# Electric_schematic.net
KiCad netlist of a schematic drawn in Altium Designer
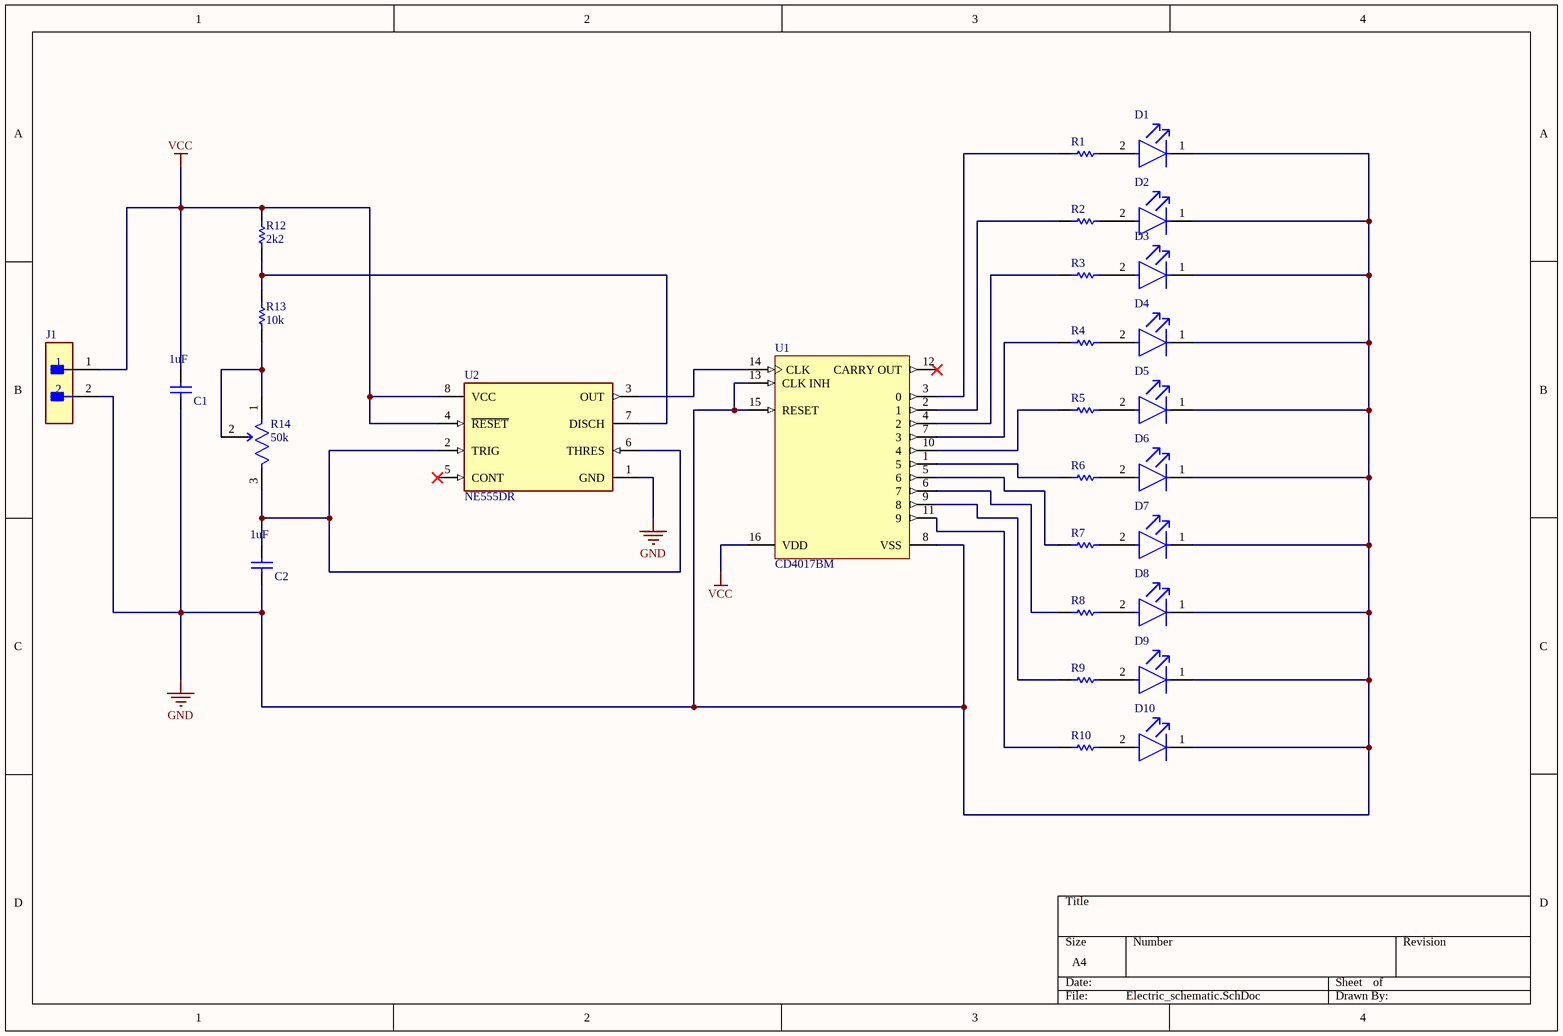
[diagram p0: Electric_schematic.SchDoc]

(export (version "E")
  (design (tool "Eeschema 10.0.6"))
  (components
    (comp (ref "C1")
      (value "1uF")
      (footprint "CAPC2013X135X45LL10T25")
      (fields (field (name "MANUFACTURER") "Murata") (field (name "PART NUMBER") "GRM21BR71H105KA12L"))
      (libsource (lib "Altium Content Vault") (part "CAP"))
    )
    (comp (ref "C2")
      (value "1uF")
      (footprint "CAPC2013X135X45LL10T25")
      (fields (field (name "MANUFACTURER") "Murata") (field (name "PART NUMBER") "GRM21BR71H105KA12L"))
      (libsource (lib "Altium Content Vault") (part "CAP"))
    )
    (comp (ref "D1")
      (value "HLMP-1301")
      (footprint "FP-HLMP-1301-MFG")
      (description "LED RED DIFFUSED T-1 T/H")
      (fields
        (field (name "OCTOPART") "https://octopart.com/hlmp-1301-broadcom-71130345")
        (field (name "MANUFACTURER") "Broadcom")
      )
      (libsource (lib "Altium Content Vault") (part "8706943c75ba83719d021d2fdc84c58"))
    )
    (comp (ref "D2")
      (value "HLMP-1301")
      (footprint "FP-HLMP-1301-MFG")
      (description "LED RED DIFFUSED T-1 T/H")
      (fields
        (field (name "OCTOPART") "https://octopart.com/hlmp-1301-broadcom-71130345")
        (field (name "MANUFACTURER") "Broadcom")
      )
      (libsource (lib "Altium Content Vault") (part "8706943c75ba83719d021d2fdc84c58"))
    )
    (comp (ref "D3")
      (value "HLMP-1301")
      (footprint "FP-HLMP-1301-MFG")
      (description "LED RED DIFFUSED T-1 T/H")
      (fields
        (field (name "OCTOPART") "https://octopart.com/hlmp-1301-broadcom-71130345")
        (field (name "MANUFACTURER") "Broadcom")
      )
      (libsource (lib "Altium Content Vault") (part "8706943c75ba83719d021d2fdc84c58"))
    )
    (comp (ref "D4")
      (value "HLMP-1301")
      (footprint "FP-HLMP-1301-MFG")
      (description "LED RED DIFFUSED T-1 T/H")
      (fields
        (field (name "OCTOPART") "https://octopart.com/hlmp-1301-broadcom-71130345")
        (field (name "MANUFACTURER") "Broadcom")
      )
      (libsource (lib "Altium Content Vault") (part "8706943c75ba83719d021d2fdc84c58"))
    )
    (comp (ref "D5")
      (value "HLMP-1301")
      (footprint "FP-HLMP-1301-MFG")
      (description "LED RED DIFFUSED T-1 T/H")
      (fields
        (field (name "OCTOPART") "https://octopart.com/hlmp-1301-broadcom-71130345")
        (field (name "MANUFACTURER") "Broadcom")
      )
      (libsource (lib "Altium Content Vault") (part "8706943c75ba83719d021d2fdc84c58"))
    )
    (comp (ref "D6")
      (value "HLMP-1301")
      (footprint "FP-HLMP-1301-MFG")
      (description "LED RED DIFFUSED T-1 T/H")
      (fields
        (field (name "OCTOPART") "https://octopart.com/hlmp-1301-broadcom-71130345")
        (field (name "MANUFACTURER") "Broadcom")
      )
      (libsource (lib "Altium Content Vault") (part "8706943c75ba83719d021d2fdc84c58"))
    )
    (comp (ref "D7")
      (value "HLMP-1301")
      (footprint "FP-HLMP-1301-MFG")
      (description "LED RED DIFFUSED T-1 T/H")
      (fields
        (field (name "OCTOPART") "https://octopart.com/hlmp-1301-broadcom-71130345")
        (field (name "MANUFACTURER") "Broadcom")
      )
      (libsource (lib "Altium Content Vault") (part "8706943c75ba83719d021d2fdc84c58"))
    )
    (comp (ref "D8")
      (value "HLMP-1301")
      (footprint "FP-HLMP-1301-MFG")
      (description "LED RED DIFFUSED T-1 T/H")
      (fields
        (field (name "OCTOPART") "https://octopart.com/hlmp-1301-broadcom-71130345")
        (field (name "MANUFACTURER") "Broadcom")
      )
      (libsource (lib "Altium Content Vault") (part "8706943c75ba83719d021d2fdc84c58"))
    )
    (comp (ref "D9")
      (value "HLMP-1301")
      (footprint "FP-HLMP-1301-MFG")
      (description "LED RED DIFFUSED T-1 T/H")
      (fields
        (field (name "OCTOPART") "https://octopart.com/hlmp-1301-broadcom-71130345")
        (field (name "MANUFACTURER") "Broadcom")
      )
      (libsource (lib "Altium Content Vault") (part "8706943c75ba83719d021d2fdc84c58"))
    )
    (comp (ref "D10")
      (value "HLMP-1301")
      (footprint "FP-HLMP-1301-MFG")
      (description "LED RED DIFFUSED T-1 T/H")
      (fields
        (field (name "OCTOPART") "https://octopart.com/hlmp-1301-broadcom-71130345")
        (field (name "MANUFACTURER") "Broadcom")
      )
      (libsource (lib "Altium Content Vault") (part "8706943c75ba83719d021d2fdc84c58"))
    )
    (comp (ref "J1")
      (value "M20-9990246")
      (footprint "FP-M20-9990246-MFG")
      (description "CONN HEADER VERT 2POS 2.54MM")
      (fields
        (field (name "OCTOPART") "https://octopart.com/m20-9990246-harwin-2590635")
        (field (name "MANUFACTURER") "Harwin")
      )
      (libsource (lib "Altium Content Vault") (part "3bc925449376181038e59eaffc5286c"))
    )
    (comp (ref "R1")
      (value "RC0805FR-071KL")
      (footprint "RESC2013X60X35ML10T20")
      (description "Chip Resistor, 1 KOhm, +/- 1%, 125 mW, -55 to 155 degC, 0805 (2012 Metric), RoHS, Tape and Reel")
      (fields (field (name "TOLERANCE") "1%") (field (name "MANUFACTURER") "Yageo"))
      (libsource (lib "Altium Content Vault") (part "RES-2"))
    )
    (comp (ref "R2")
      (value "RC0805FR-071KL")
      (footprint "RESC2013X60X35ML10T20")
      (description "Chip Resistor, 1 KOhm, +/- 1%, 125 mW, -55 to 155 degC, 0805 (2012 Metric), RoHS, Tape and Reel")
      (fields (field (name "TOLERANCE") "1%") (field (name "MANUFACTURER") "Yageo"))
      (libsource (lib "Altium Content Vault") (part "RES-2"))
    )
    (comp (ref "R3")
      (value "RC0805FR-071KL")
      (footprint "RESC2013X60X35ML10T20")
      (description "Chip Resistor, 1 KOhm, +/- 1%, 125 mW, -55 to 155 degC, 0805 (2012 Metric), RoHS, Tape and Reel")
      (fields (field (name "TOLERANCE") "1%") (field (name "MANUFACTURER") "Yageo"))
      (libsource (lib "Altium Content Vault") (part "RES-2"))
    )
    (comp (ref "R4")
      (value "RC0805FR-071KL")
      (footprint "RESC2013X60X35ML10T20")
      (description "Chip Resistor, 1 KOhm, +/- 1%, 125 mW, -55 to 155 degC, 0805 (2012 Metric), RoHS, Tape and Reel")
      (fields (field (name "TOLERANCE") "1%") (field (name "MANUFACTURER") "Yageo"))
      (libsource (lib "Altium Content Vault") (part "RES-2"))
    )
    (comp (ref "R5")
      (value "RC0805FR-071KL")
      (footprint "RESC2013X60X35ML10T20")
      (description "Chip Resistor, 1 KOhm, +/- 1%, 125 mW, -55 to 155 degC, 0805 (2012 Metric), RoHS, Tape and Reel")
      (fields (field (name "TOLERANCE") "1%") (field (name "MANUFACTURER") "Yageo"))
      (libsource (lib "Altium Content Vault") (part "RES-2"))
    )
    (comp (ref "R6")
      (value "RC0805FR-071KL")
      (footprint "RESC2013X60X35ML10T20")
      (description "Chip Resistor, 1 KOhm, +/- 1%, 125 mW, -55 to 155 degC, 0805 (2012 Metric), RoHS, Tape and Reel")
      (fields (field (name "TOLERANCE") "1%") (field (name "MANUFACTURER") "Yageo"))
      (libsource (lib "Altium Content Vault") (part "RES-2"))
    )
    (comp (ref "R7")
      (value "RC0805FR-071KL")
      (footprint "RESC2013X60X35ML10T20")
      (description "Chip Resistor, 1 KOhm, +/- 1%, 125 mW, -55 to 155 degC, 0805 (2012 Metric), RoHS, Tape and Reel")
      (fields (field (name "TOLERANCE") "1%") (field (name "MANUFACTURER") "Yageo"))
      (libsource (lib "Altium Content Vault") (part "RES-2"))
    )
    (comp (ref "R8")
      (value "RC0805FR-071KL")
      (footprint "RESC2013X60X35ML10T20")
      (description "Chip Resistor, 1 KOhm, +/- 1%, 125 mW, -55 to 155 degC, 0805 (2012 Metric), RoHS, Tape and Reel")
      (fields (field (name "TOLERANCE") "1%") (field (name "MANUFACTURER") "Yageo"))
      (libsource (lib "Altium Content Vault") (part "RES-2"))
    )
    (comp (ref "R9")
      (value "RC0805FR-071KL")
      (footprint "RESC2013X60X35ML10T20")
      (description "Chip Resistor, 1 KOhm, +/- 1%, 125 mW, -55 to 155 degC, 0805 (2012 Metric), RoHS, Tape and Reel")
      (fields (field (name "TOLERANCE") "1%") (field (name "MANUFACTURER") "Yageo"))
      (libsource (lib "Altium Content Vault") (part "RES-2"))
    )
    (comp (ref "R10")
      (value "RC0805FR-071KL")
      (footprint "RESC2013X60X35ML10T20")
      (description "Chip Resistor, 1 KOhm, +/- 1%, 125 mW, -55 to 155 degC, 0805 (2012 Metric), RoHS, Tape and Reel")
      (fields (field (name "TOLERANCE") "1%") (field (name "MANUFACTURER") "Yageo"))
      (libsource (lib "Altium Content Vault") (part "RES-2"))
    )
    (comp (ref "R12")
      (value "2k2")
      (footprint "RESC2013X60X35ML10T20")
      (description "Chip Resistor, 1 KOhm, +/- 1%, 125 mW, -55 to 155 degC, 0805 (2012 Metric), RoHS, Tape and Reel")
      (fields (field (name "TOLERANCE") "1%") (field (name "MANUFACTURER") "Yageo"))
      (libsource (lib "Altium Content Vault") (part "RES-2"))
    )
    (comp (ref "R13")
      (value "10k")
      (footprint "RESC2013X60X35ML10T20")
      (description "Chip Resistor, 1 KOhm, +/- 1%, 125 mW, -55 to 155 degC, 0805 (2012 Metric), RoHS, Tape and Reel")
      (fields (field (name "TOLERANCE") "1%") (field (name "MANUFACTURER") "Yageo"))
      (libsource (lib "Altium Content Vault") (part "RES-2"))
    )
    (comp (ref "R14")
      (value "50k")
      (footprint "FP-3386P-MFG")
      (description "TRIMMER 100K OHM 0.5W PC PIN TOP")
      (fields (field (name "TOLERANCE") "10%"))
      (libsource (lib "Altium Content Vault") (part "13357d81287629c2fd191d242cfa50c"))
    )
    (comp (ref "U1")
      (value "CD4017BM")
      (footprint "D0016A_N")
      (description "CMOS Decade Counter with 10 Decoded Outputs, D0016A, TUBE")
      (fields
        (field (name "GENERIC PART NUMBER") "CD4017B")
        (field (name "MANUFACTURER") "Texas Instruments")
      )
      (libsource (lib "Altium Content Vault") (part "TI-CD4017B-16"))
    )
    (comp (ref "U2")
      (value "NE555DR")
      (footprint "FP-D0008A-IPC_A")
      (description "IC OSC SGL TIMER 100KHZ 8-SOIC")
      (libsource (lib "Altium Content Vault") (part "a29bba90211dec1890110b94dad7d53"))
    )
  )
  (nets
    (net (code "1") (name "GND") (class "Default")
      (node (ref "C1") (pin "2") (pinfunction "2_2") (pintype "passive"))
      (node (ref "C2") (pin "2") (pinfunction "2_2") (pintype "passive"))
      (node (ref "D1") (pin "1") (pinfunction "C_1") (pintype "passive"))
      (node (ref "D10") (pin "1") (pinfunction "C_1") (pintype "passive"))
      (node (ref "D2") (pin "1") (pinfunction "C_1") (pintype "passive"))
      (node (ref "D3") (pin "1") (pinfunction "C_1") (pintype "passive"))
      (node (ref "D4") (pin "1") (pinfunction "C_1") (pintype "passive"))
      (node (ref "D5") (pin "1") (pinfunction "C_1") (pintype "passive"))
      (node (ref "D6") (pin "1") (pinfunction "C_1") (pintype "passive"))
      (node (ref "D7") (pin "1") (pinfunction "C_1") (pintype "passive"))
      (node (ref "D8") (pin "1") (pinfunction "C_1") (pintype "passive"))
      (node (ref "D9") (pin "1") (pinfunction "C_1") (pintype "passive"))
      (node (ref "J1") (pin "2") (pinfunction "2_2") (pintype "passive"))
      (node (ref "U1") (pin "13") (pinfunction "CLK_INH_13") (pintype "input"))
      (node (ref "U1") (pin "15") (pinfunction "RESET_15") (pintype "input"))
      (node (ref "U1") (pin "8") (pinfunction "VSS_8") (pintype "power_in"))
      (node (ref "U2") (pin "1") (pinfunction "GND_1") (pintype "power_in"))
    )
    (net (code "2") (name "Net-(D1-A)") (class "Default")
      (node (ref "D1") (pin "2") (pinfunction "A_2") (pintype "passive"))
      (node (ref "R1") (pin "2") (pinfunction "2_2") (pintype "passive"))
    )
    (net (code "3") (name "Net-(D2-A)") (class "Default")
      (node (ref "D2") (pin "2") (pinfunction "A_2") (pintype "passive"))
      (node (ref "R2") (pin "2") (pinfunction "2_2") (pintype "passive"))
    )
    (net (code "4") (name "Net-(D3-A)") (class "Default")
      (node (ref "D3") (pin "2") (pinfunction "A_2") (pintype "passive"))
      (node (ref "R3") (pin "2") (pinfunction "2_2") (pintype "passive"))
    )
    (net (code "5") (name "Net-(D4-A)") (class "Default")
      (node (ref "D4") (pin "2") (pinfunction "A_2") (pintype "passive"))
      (node (ref "R4") (pin "2") (pinfunction "2_2") (pintype "passive"))
    )
    (net (code "6") (name "Net-(D5-A)") (class "Default")
      (node (ref "D5") (pin "2") (pinfunction "A_2") (pintype "passive"))
      (node (ref "R5") (pin "2") (pinfunction "2_2") (pintype "passive"))
    )
    (net (code "7") (name "Net-(D6-A)") (class "Default")
      (node (ref "D6") (pin "2") (pinfunction "A_2") (pintype "passive"))
      (node (ref "R6") (pin "2") (pinfunction "2_2") (pintype "passive"))
    )
    (net (code "8") (name "Net-(D7-A)") (class "Default")
      (node (ref "D7") (pin "2") (pinfunction "A_2") (pintype "passive"))
      (node (ref "R7") (pin "2") (pinfunction "2_2") (pintype "passive"))
    )
    (net (code "9") (name "Net-(D8-A)") (class "Default")
      (node (ref "D8") (pin "2") (pinfunction "A_2") (pintype "passive"))
      (node (ref "R8") (pin "2") (pinfunction "2_2") (pintype "passive"))
    )
    (net (code "10") (name "Net-(D9-A)") (class "Default")
      (node (ref "D9") (pin "2") (pinfunction "A_2") (pintype "passive"))
      (node (ref "R9") (pin "2") (pinfunction "2_2") (pintype "passive"))
    )
    (net (code "11") (name "Net-(D10-A)") (class "Default")
      (node (ref "D10") (pin "2") (pinfunction "A_2") (pintype "passive"))
      (node (ref "R10") (pin "2") (pinfunction "2_2") (pintype "passive"))
    )
    (net (code "12") (name "Net-(R14-CCW)") (class "Default")
      (node (ref "R13") (pin "1") (pinfunction "1_1") (pintype "passive"))
      (node (ref "R14") (pin "1") (pinfunction "CCW_1") (pintype "passive"))
      (node (ref "R14") (pin "2") (pinfunction "WIPER_2") (pintype "passive"))
    )
    (net (code "13") (name "Net-(R14-CW)") (class "Default")
      (node (ref "C2") (pin "1") (pinfunction "1_1") (pintype "passive"))
      (node (ref "R14") (pin "3") (pinfunction "CW_3") (pintype "passive"))
      (node (ref "U2") (pin "2") (pinfunction "TRIG_2") (pintype "input"))
      (node (ref "U2") (pin "6") (pinfunction "THRES_6") (pintype "input"))
    )
    (net (code "14") (name "Net-(U1-0)") (class "Default")
      (node (ref "R1") (pin "1") (pinfunction "1_1") (pintype "passive"))
      (node (ref "U1") (pin "3") (pinfunction "0_3") (pintype "output"))
    )
    (net (code "15") (name "Net-(U1-1)") (class "Default")
      (node (ref "R2") (pin "1") (pinfunction "1_1") (pintype "passive"))
      (node (ref "U1") (pin "2") (pinfunction "1_2") (pintype "output"))
    )
    (net (code "16") (name "Net-(U1-2)") (class "Default")
      (node (ref "R3") (pin "1") (pinfunction "1_1") (pintype "passive"))
      (node (ref "U1") (pin "4") (pinfunction "2_4") (pintype "output"))
    )
    (net (code "17") (name "Net-(U1-3)") (class "Default")
      (node (ref "R4") (pin "1") (pinfunction "1_1") (pintype "passive"))
      (node (ref "U1") (pin "7") (pinfunction "3_7") (pintype "output"))
    )
    (net (code "18") (name "Net-(U1-4)") (class "Default")
      (node (ref "R5") (pin "1") (pinfunction "1_1") (pintype "passive"))
      (node (ref "U1") (pin "10") (pinfunction "4_10") (pintype "output"))
    )
    (net (code "19") (name "Net-(U1-5)") (class "Default")
      (node (ref "R6") (pin "1") (pinfunction "1_1") (pintype "passive"))
      (node (ref "U1") (pin "1") (pinfunction "5_1") (pintype "output"))
    )
    (net (code "20") (name "Net-(U1-6)") (class "Default")
      (node (ref "R7") (pin "1") (pinfunction "1_1") (pintype "passive"))
      (node (ref "U1") (pin "5") (pinfunction "6_5") (pintype "output"))
    )
    (net (code "21") (name "Net-(U1-7)") (class "Default")
      (node (ref "R8") (pin "1") (pinfunction "1_1") (pintype "passive"))
      (node (ref "U1") (pin "6") (pinfunction "7_6") (pintype "output"))
    )
    (net (code "22") (name "Net-(U1-8)") (class "Default")
      (node (ref "R9") (pin "1") (pinfunction "1_1") (pintype "passive"))
      (node (ref "U1") (pin "9") (pinfunction "8_9") (pintype "output"))
    )
    (net (code "23") (name "Net-(U1-9)") (class "Default")
      (node (ref "R10") (pin "1") (pinfunction "1_1") (pintype "passive"))
      (node (ref "U1") (pin "11") (pinfunction "9_11") (pintype "output"))
    )
    (net (code "24") (name "Net-(U1-CLK)") (class "Default")
      (node (ref "U1") (pin "14") (pinfunction "CLK_14") (pintype "input"))
      (node (ref "U2") (pin "3") (pinfunction "OUT_3") (pintype "output"))
    )
    (net (code "25") (name "Net-(U2-DISCH)") (class "Default")
      (node (ref "R12") (pin "1") (pinfunction "1_1") (pintype "passive"))
      (node (ref "R13") (pin "2") (pinfunction "2_2") (pintype "passive"))
      (node (ref "U2") (pin "7") (pinfunction "DISCH_7") (pintype "open_collector"))
    )
    (net (code "26") (name "VCC") (class "Default")
      (node (ref "C1") (pin "1") (pinfunction "1_1") (pintype "passive"))
      (node (ref "J1") (pin "1") (pinfunction "1_1") (pintype "passive"))
      (node (ref "R12") (pin "2") (pinfunction "2_2") (pintype "passive"))
      (node (ref "U1") (pin "16") (pinfunction "VDD_16") (pintype "power_in"))
      (node (ref "U2") (pin "4") (pinfunction "~{RESET}_4") (pintype "input"))
      (node (ref "U2") (pin "8") (pinfunction "VCC_8") (pintype "power_in"))
    )
    (net (code "27") (name "unconnected-(U1-CARRY_OUT-Pad12)") (class "Default")
      (node (ref "U1") (pin "12") (pinfunction "CARRY_OUT_12") (pintype "output+no_connect"))
    )
    (net (code "28") (name "unconnected-(U2-CONT-Pad5)") (class "Default")
      (node (ref "U2") (pin "5") (pinfunction "CONT_5") (pintype "input+no_connect"))
    )
  )
)
